# LoRa-Messenger-v1_1.net
KiCad netlist of a schematic drawn in EAGLE
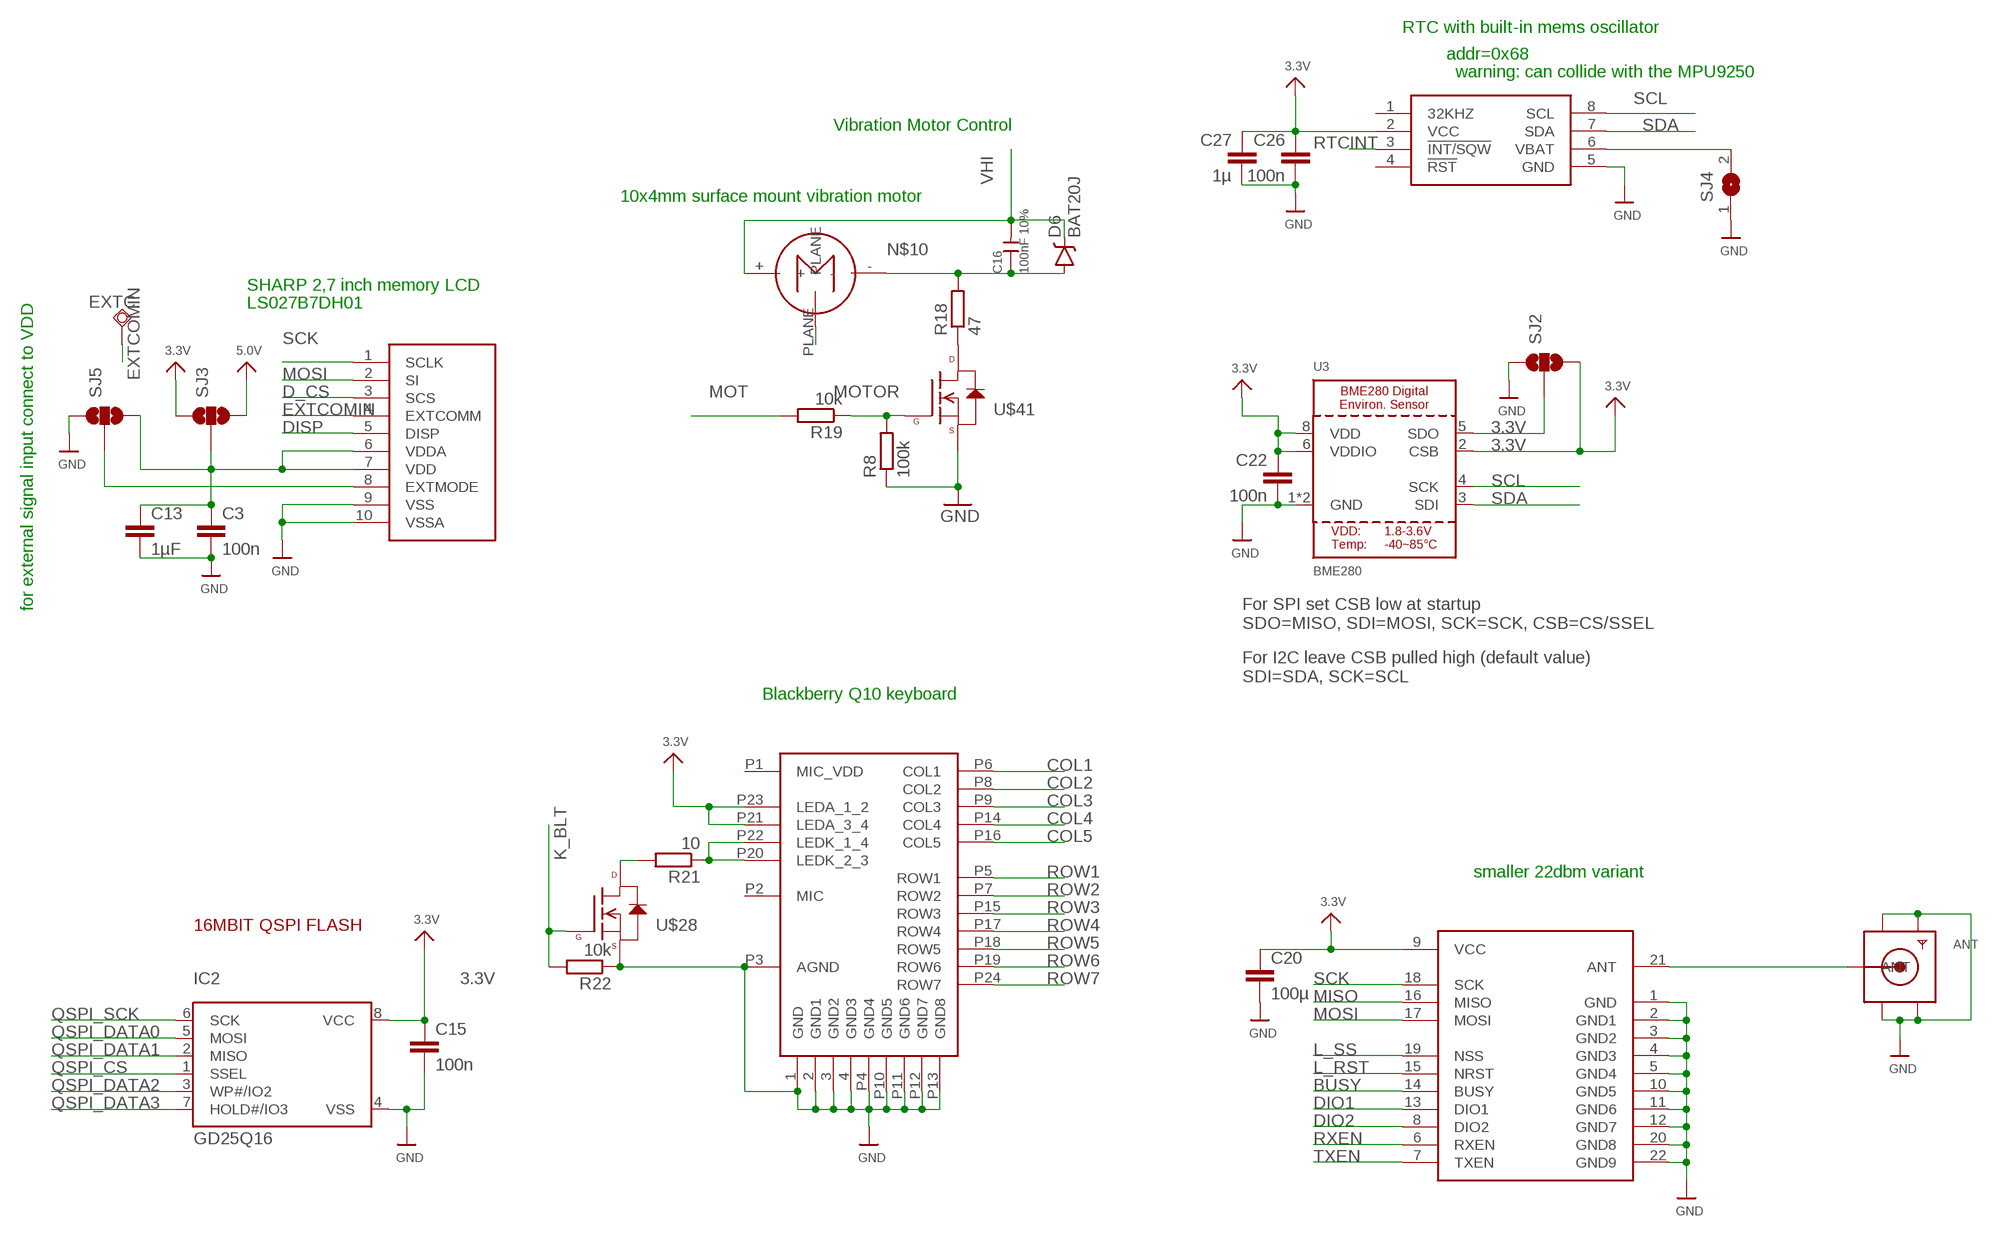
[diagram p0: schematic, sheet 1, part 1 of 3]
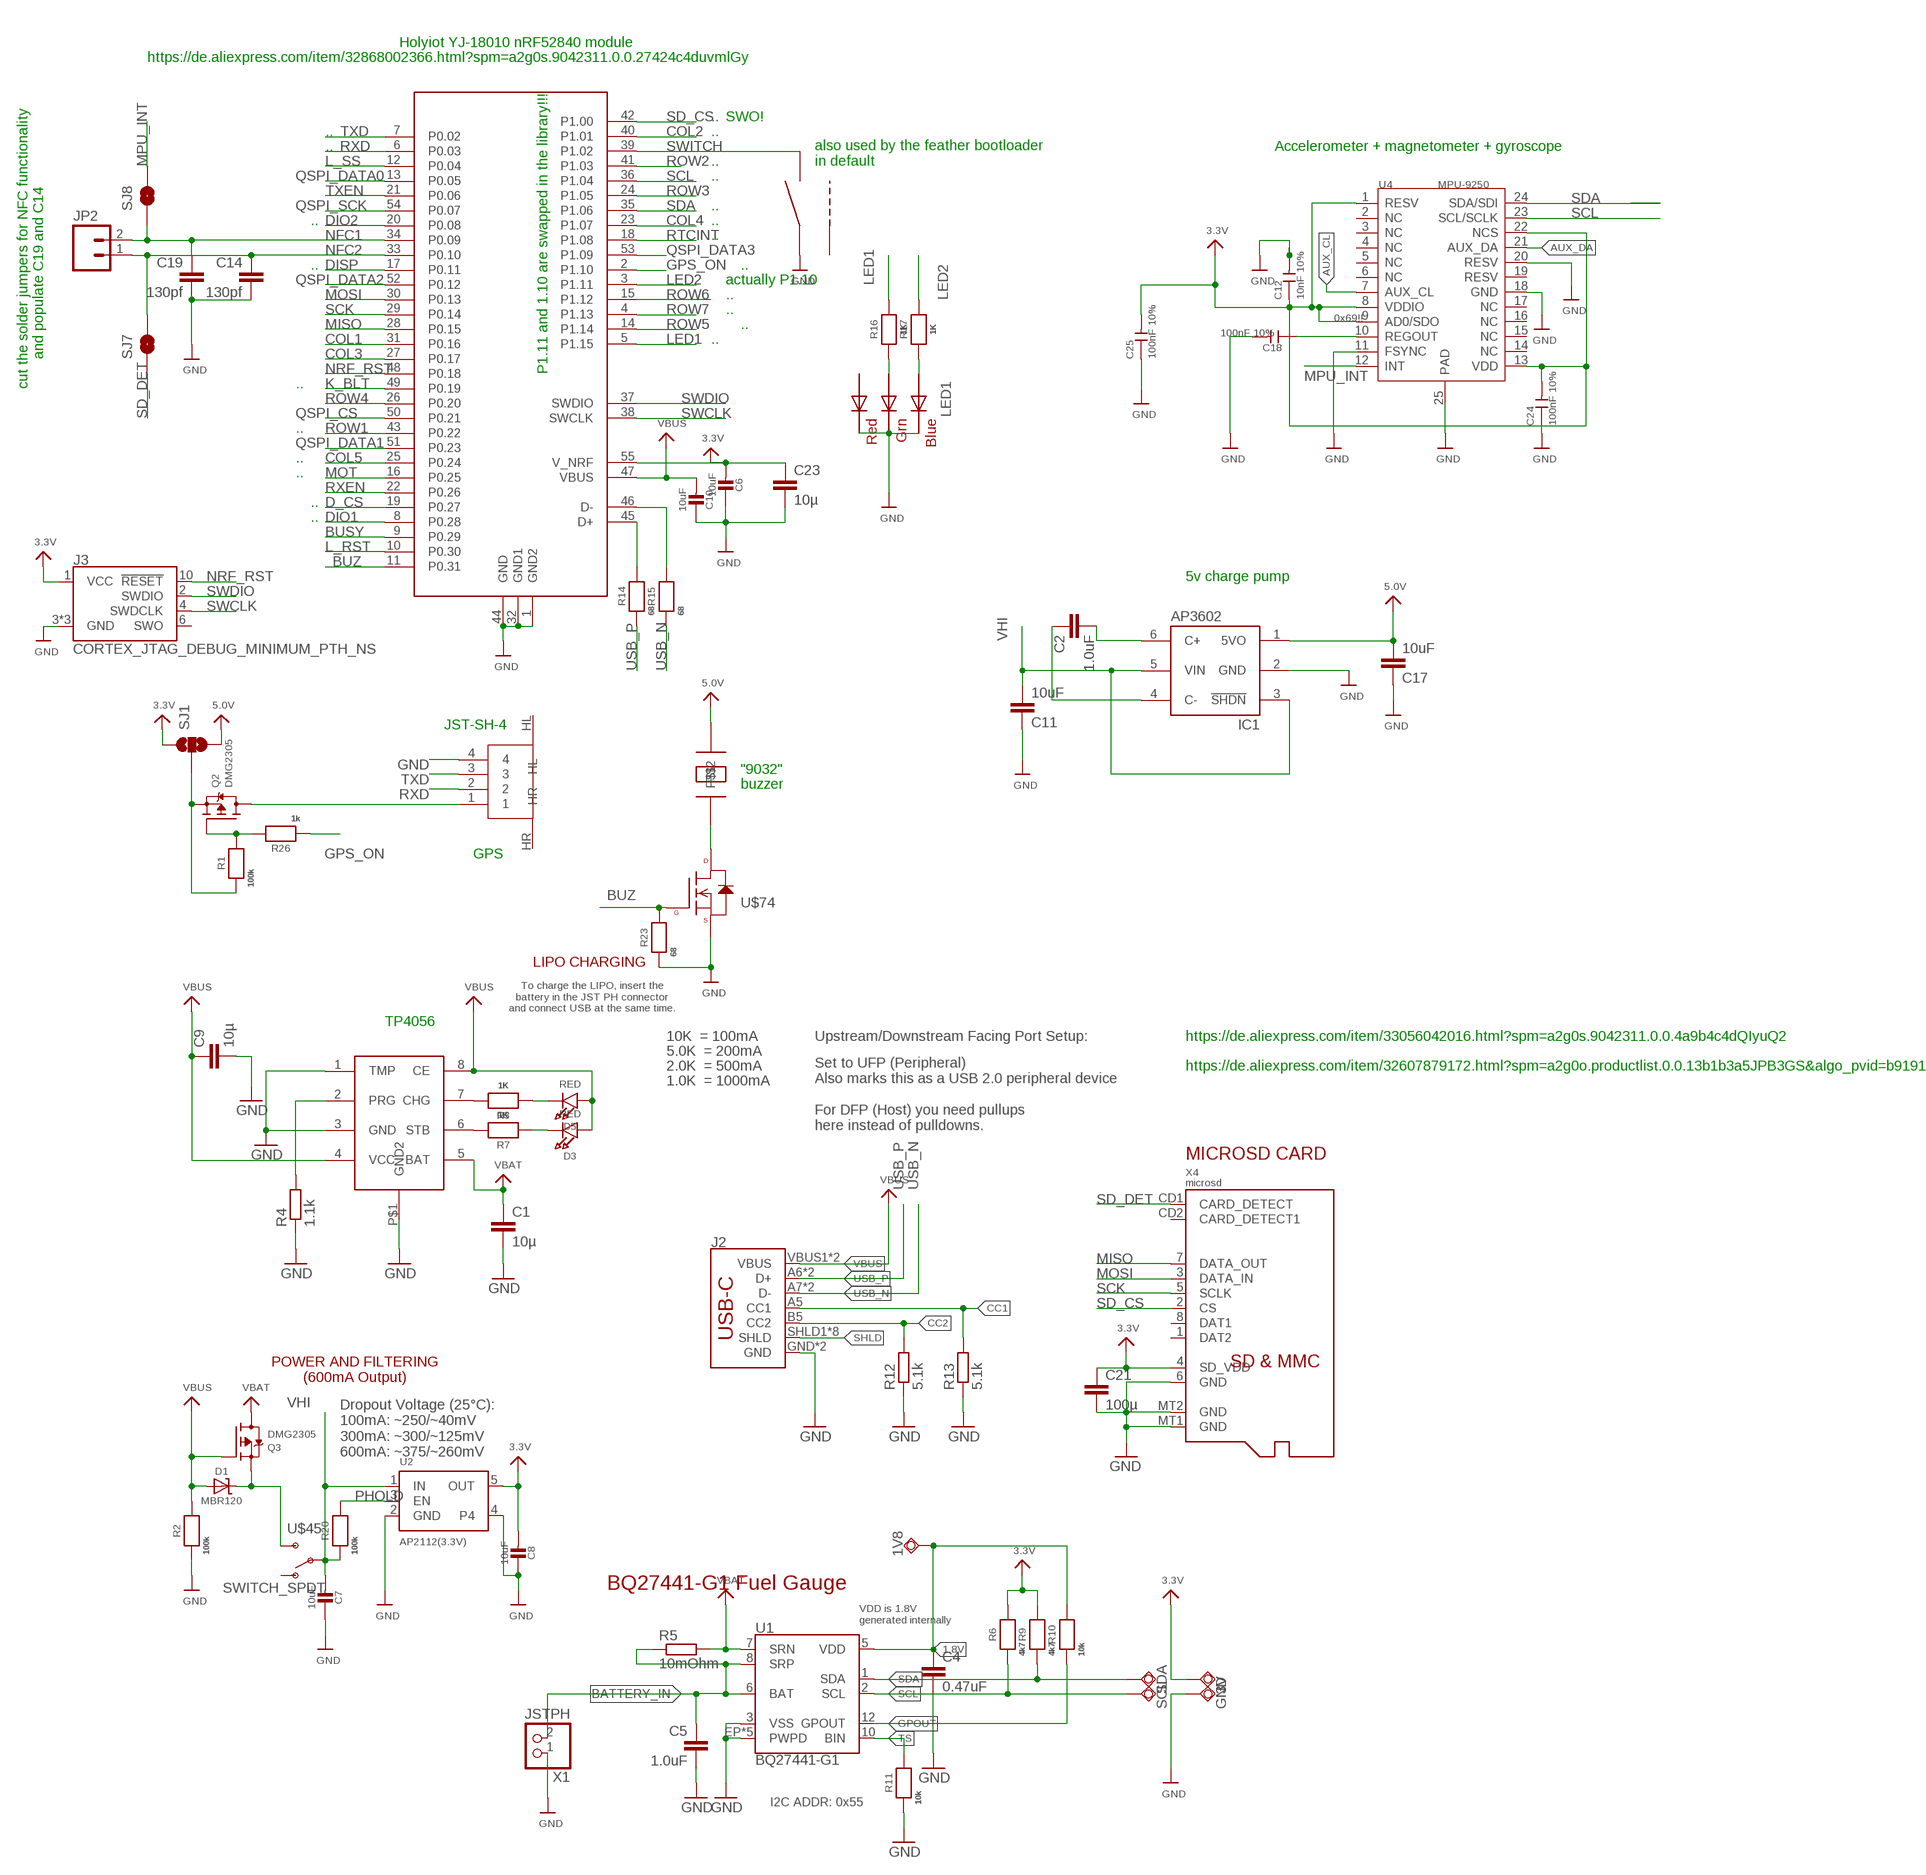
[diagram p1: schematic, sheet 1, part 2 of 3]
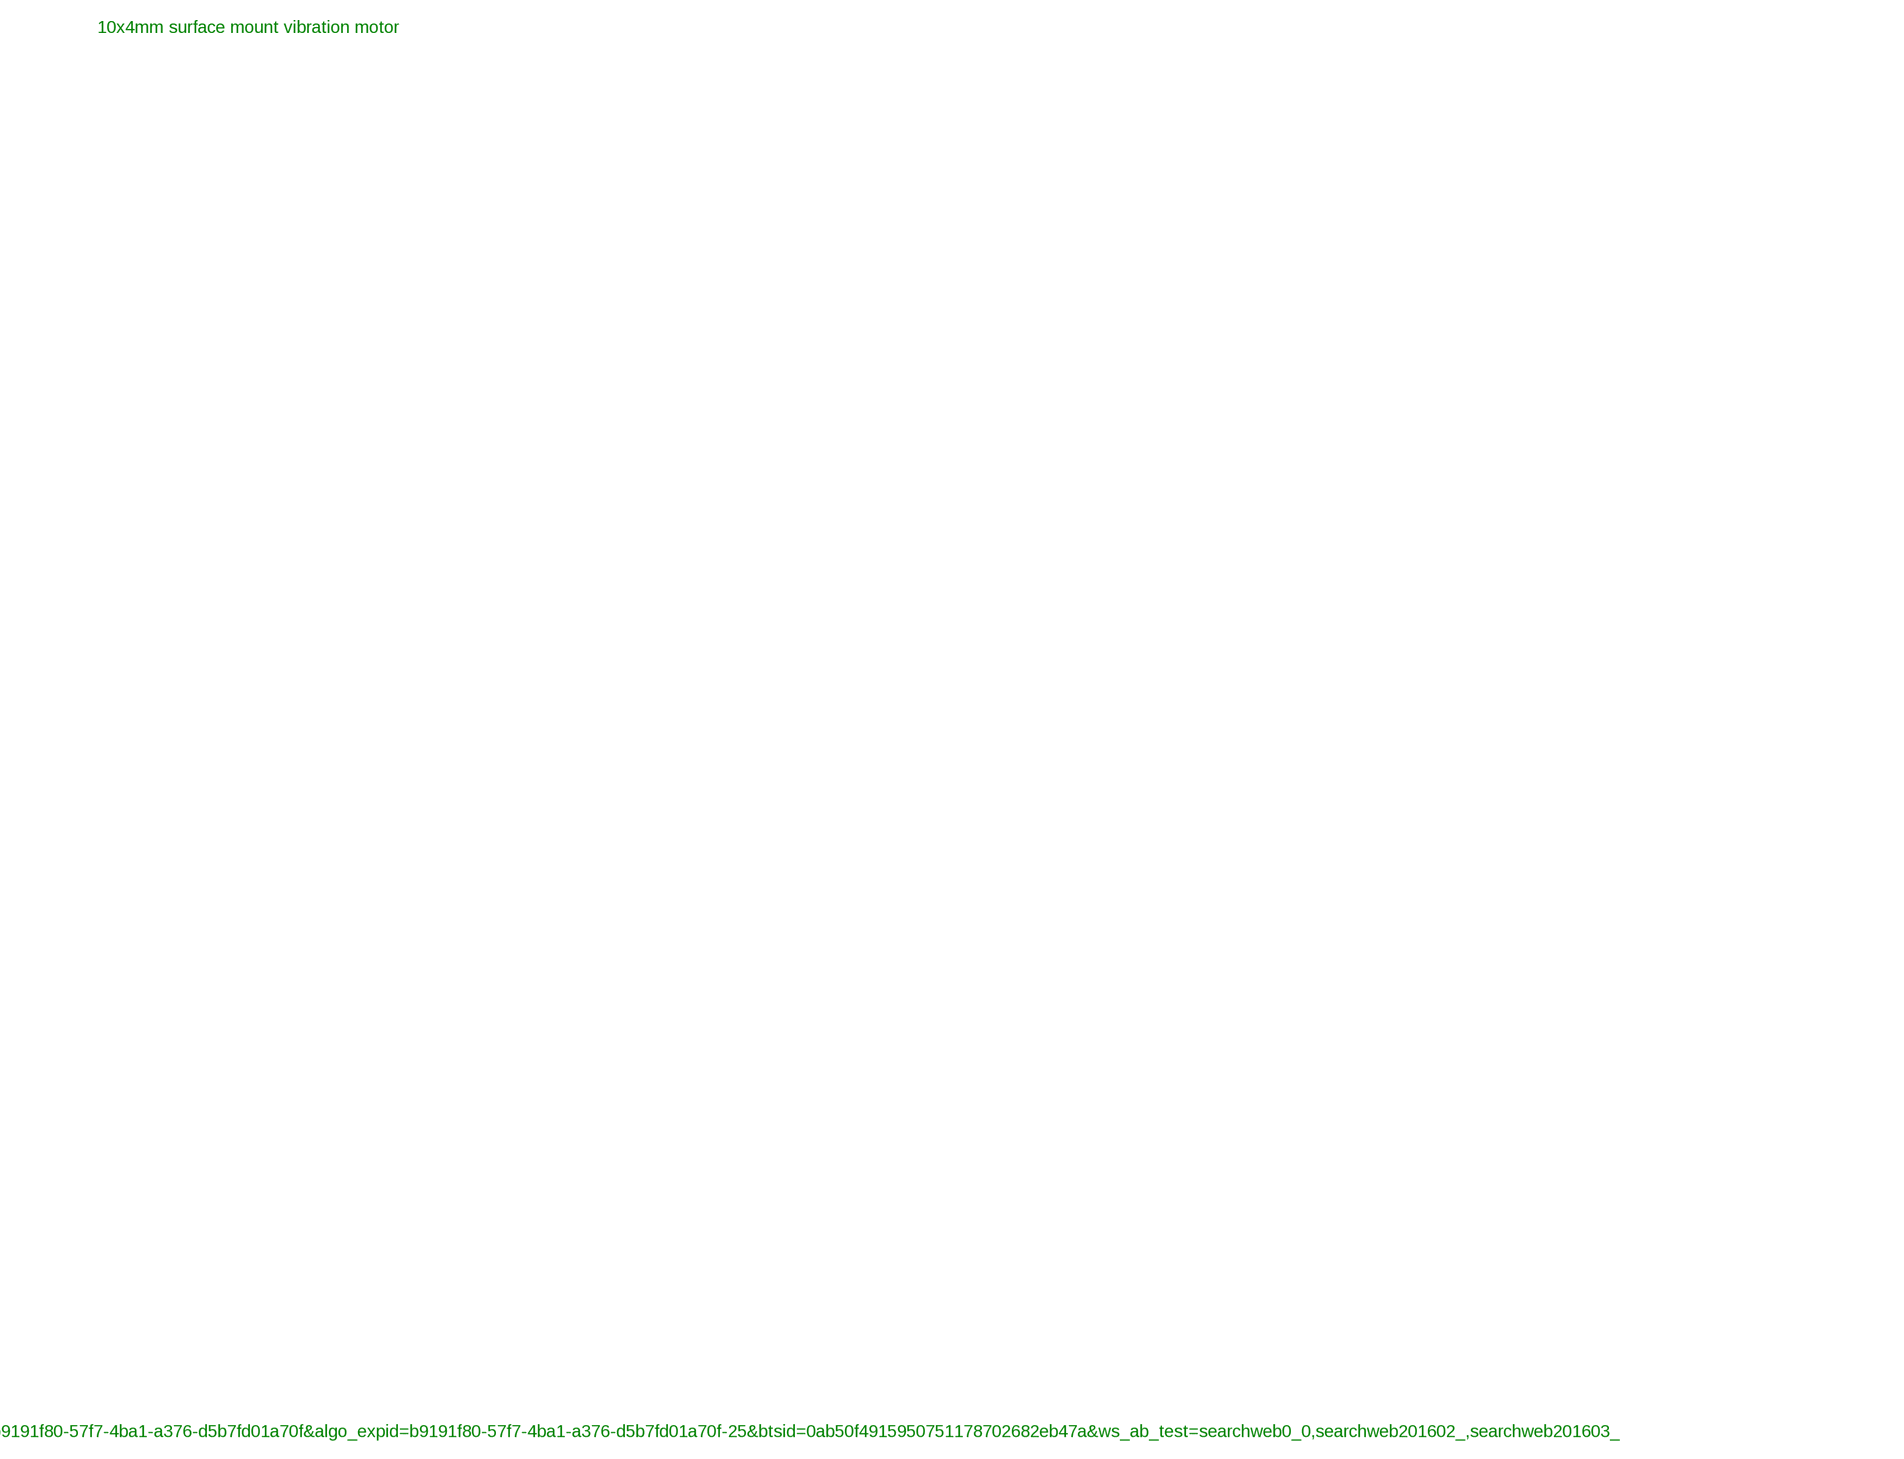
[diagram p2: schematic, sheet 1, part 3 of 3]

(export (version "E")
  (design (tool "Eeschema 10.0.6"))
  (components
    (comp (ref "1V8")
      (value "TPSQTP13R")
      (footprint "eagle-import:TP13R")
      (libsource (lib "eagle-import") (part "TPSQTP13R"))
    )
    (comp (ref "3V")
      (value "TPSQTP13R")
      (footprint "eagle-import:TP13R")
      (libsource (lib "eagle-import") (part "TPSQTP13R"))
    )
    (comp (ref "ANT")
      (value "SMACONNECTOR_EDGE")
      (footprint "eagle-import:SMA_EDGELAUNCH")
      (libsource (lib "eagle-import") (part "SMACONNECTOR_EDGE"))
    )
    (comp (ref "C1")
      (value "10µ")
      (footprint "eagle-import:C0805")
      (libsource (lib "eagle-import") (part "rcl_334_C-EUC0805"))
    )
    (comp (ref "C2")
      (value "1.0uF")
      (footprint "eagle-import:0603-CAP")
      (libsource (lib "eagle-import") (part "1.0UF-16V-10%(0603)"))
    )
    (comp (ref "C3")
      (value "100n")
      (footprint "eagle-import:C0402")
      (libsource (lib "eagle-import") (part "C-EUC0402"))
    )
    (comp (ref "C4")
      (value "0.47uF")
      (footprint "eagle-import:0603-CAP")
      (libsource (lib "eagle-import") (part "CAP0603-CAP"))
    )
    (comp (ref "C5")
      (value "1.0uF")
      (footprint "eagle-import:0603-CAP")
      (libsource (lib "eagle-import") (part "1.0UF-16V-10%(0603)"))
    )
    (comp (ref "C6")
      (value "10uF")
      (footprint "eagle-import:0805-NO")
      (libsource (lib "eagle-import") (part "CAP_CERAMIC0805-NOOUTLINE"))
    )
    (comp (ref "C7")
      (value "10uF")
      (footprint "eagle-import:0805-NO")
      (libsource (lib "eagle-import") (part "CAP_CERAMIC0805-NOOUTLINE"))
    )
    (comp (ref "C8")
      (value "10uF")
      (footprint "eagle-import:0805-NO")
      (libsource (lib "eagle-import") (part "CAP_CERAMIC0805-NOOUTLINE"))
    )
    (comp (ref "C9")
      (value "10µ")
      (footprint "eagle-import:C0805")
      (libsource (lib "eagle-import") (part "rcl_334_C-EUC0805"))
    )
    (comp (ref "C10")
      (value "10uF")
      (footprint "eagle-import:0805-NO")
      (libsource (lib "eagle-import") (part "CAP_CERAMIC0805-NOOUTLINE"))
    )
    (comp (ref "C11")
      (value "10uF")
      (footprint "eagle-import:0603-CAP")
      (libsource (lib "eagle-import") (part "1.0UF-16V-10%(0603)"))
    )
    (comp (ref "C12")
      (value "10nF 10%")
      (footprint "eagle-import:C0603")
      (libsource (lib "eagle-import") (part "CAP-0603"))
    )
    (comp (ref "C13")
      (value "1µF")
      (footprint "eagle-import:C0402")
      (libsource (lib "eagle-import") (part "C-EUC0402"))
    )
    (comp (ref "C14")
      (value "130pf")
      (footprint "eagle-import:0603-CAP")
      (libsource (lib "eagle-import") (part "1.0UF-16V-10%(0603)"))
    )
    (comp (ref "C15")
      (value "100n")
      (footprint "eagle-import:C0402")
      (libsource (lib "eagle-import") (part "C-EUC0402"))
    )
    (comp (ref "C16")
      (value "100nF 10%")
      (footprint "eagle-import:C0603")
      (libsource (lib "eagle-import") (part "CAP-0603"))
    )
    (comp (ref "C17")
      (value "10uF")
      (footprint "eagle-import:0603-CAP")
      (libsource (lib "eagle-import") (part "1.0UF-16V-10%(0603)"))
    )
    (comp (ref "C18")
      (value "100nF 10%")
      (footprint "eagle-import:C0603")
      (libsource (lib "eagle-import") (part "CAP-0603"))
    )
    (comp (ref "C19")
      (value "130pf")
      (footprint "eagle-import:0603-CAP")
      (libsource (lib "eagle-import") (part "1.0UF-16V-10%(0603)"))
    )
    (comp (ref "C20")
      (value "100µ")
      (footprint "eagle-import:C1206")
      (libsource (lib "eagle-import") (part "rcl_334_C-EUC1206"))
    )
    (comp (ref "C21")
      (value "100µ")
      (footprint "eagle-import:C1206")
      (libsource (lib "eagle-import") (part "rcl_334_C-EUC1206"))
    )
    (comp (ref "C22")
      (value "100n")
      (footprint "eagle-import:0603-CAP")
      (libsource (lib "eagle-import") (part "1.0UF-16V-10%(0603)"))
    )
    (comp (ref "C23")
      (value "10µ")
      (footprint "eagle-import:C0805")
      (libsource (lib "eagle-import") (part "rcl_334_C-EUC0805"))
    )
    (comp (ref "C24")
      (value "100nF 10%")
      (footprint "eagle-import:C0603")
      (libsource (lib "eagle-import") (part "CAP-0603"))
    )
    (comp (ref "C25")
      (value "100nF 10%")
      (footprint "eagle-import:C0603")
      (libsource (lib "eagle-import") (part "CAP-0603"))
    )
    (comp (ref "C26")
      (value "100n")
      (footprint "eagle-import:0603-CAP")
      (libsource (lib "eagle-import") (part "1.0UF-16V-10%(0603)"))
    )
    (comp (ref "C27")
      (value "1µ")
      (footprint "eagle-import:0603-CAP")
      (libsource (lib "eagle-import") (part "1.0UF-16V-10%(0603)"))
    )
    (comp (ref "D1")
      (value "MBR120")
      (footprint "eagle-import:SOD-123")
      (libsource (lib "eagle-import") (part "DIODE-SCHOTTKYSOD-123"))
    )
    (comp (ref "D3")
      (value "RED")
      (footprint "eagle-import:CHIPLED_0805_NOOUTLINE")
      (libsource (lib "eagle-import") (part "LED0805_NOOUTLINE"))
    )
    (comp (ref "D5")
      (value "RED")
      (footprint "eagle-import:CHIPLED_0805_NOOUTLINE")
      (libsource (lib "eagle-import") (part "LED0805_NOOUTLINE"))
    )
    (comp (ref "D6")
      (value "BAT20J")
      (footprint "eagle-import:SOD-323")
      (libsource (lib "eagle-import") (part "DIODE-SCHOTTKY-BAT20J"))
    )
    (comp (ref "DWN2")
      (value "LS12T2")
      (footprint "eagle-import:LS12T2")
      (libsource (lib "eagle-import") (part "LS12T2"))
    )
    (comp (ref "EXTC.")
      (value "TPSQTP13R")
      (footprint "eagle-import:TP13R")
      (libsource (lib "eagle-import") (part "TPSQTP13R"))
    )
    (comp (ref "GND")
      (value "TPSQTP13R")
      (footprint "eagle-import:TP13R")
      (libsource (lib "eagle-import") (part "TPSQTP13R"))
    )
    (comp (ref "IC1")
      (value "AP3602")
      (footprint "eagle-import:SOT23-6")
      (libsource (lib "eagle-import") (part "AP3602"))
    )
    (comp (ref "IC2")
      (value "GD25Q16")
      (footprint "eagle-import:USON8")
      (libsource (lib "eagle-import") (part "SPIFLASH_8PINUX"))
    )
    (comp (ref "J2")
      (value "USB_C16PIN")
      (footprint "eagle-import:USB-C-16P")
      (libsource (lib "eagle-import") (part "USB_C16PIN"))
    )
    (comp (ref "J3")
      (value "CORTEX_JTAG_DEBUG_MINIMUM_PTH_NS")
      (footprint "eagle-import:2X5-PTH-1.27MM-NO_SILK")
      (libsource (lib "eagle-import") (part "CORTEX_JTAG_DEBUG_MINIMUM_PTH_NS"))
    )
    (comp (ref "JP2")
      (value "M02PTH")
      (footprint "eagle-import:1X02")
      (libsource (lib "eagle-import") (part "M02PTH"))
    )
    (comp (ref "LED1")
      (value "RGBLED5050")
      (footprint "eagle-import:RGBLED5050")
      (libsource (lib "eagle-import") (part "RGBLED5050"))
    )
    (comp (ref "Q2")
      (value "DMG2305")
      (footprint "eagle-import:SOT23-R")
      (libsource (lib "eagle-import") (part "MOSFET-P"))
    )
    (comp (ref "Q3")
      (value "DMG2305")
      (footprint "eagle-import:SOT23-R")
      (libsource (lib "eagle-import") (part "MOSFET-P"))
    )
    (comp (ref "R1")
      (value "100k")
      (footprint "eagle-import:0603-NO")
      (libsource (lib "eagle-import") (part "RESISTOR_0603_NOOUT"))
    )
    (comp (ref "R2")
      (value "100k")
      (footprint "eagle-import:0603-NO")
      (libsource (lib "eagle-import") (part "RESISTOR_0603_NOOUT"))
    )
    (comp (ref "R3")
      (value "1K")
      (footprint "eagle-import:0603-NO")
      (libsource (lib "eagle-import") (part "RESISTOR_0603_NOOUT"))
    )
    (comp (ref "R4")
      (value "1.1k")
      (footprint "eagle-import:R0603")
      (libsource (lib "eagle-import") (part "rcl_334_R-EU_R0603"))
    )
    (comp (ref "R5")
      (value "10mOhm")
      (footprint "eagle-import:R0805")
      (libsource (lib "eagle-import") (part "rcl_334_R-EU_R0805"))
    )
    (comp (ref "R6")
      (value "4k7")
      (footprint "eagle-import:0603-NO")
      (libsource (lib "eagle-import") (part "RESISTOR_0603_NOOUT"))
    )
    (comp (ref "R7")
      (value "1K")
      (footprint "eagle-import:0603-NO")
      (libsource (lib "eagle-import") (part "RESISTOR_0603_NOOUT"))
    )
    (comp (ref "R8")
      (value "100k")
      (footprint "eagle-import:R0603")
      (libsource (lib "eagle-import") (part "R-EU_R0603"))
    )
    (comp (ref "R9")
      (value "4k7")
      (footprint "eagle-import:0603-NO")
      (libsource (lib "eagle-import") (part "RESISTOR_0603_NOOUT"))
    )
    (comp (ref "R10")
      (value "10k")
      (footprint "eagle-import:0603-NO")
      (libsource (lib "eagle-import") (part "RESISTOR_0603_NOOUT"))
    )
    (comp (ref "R11")
      (value "10k")
      (footprint "eagle-import:0603-NO")
      (libsource (lib "eagle-import") (part "RESISTOR_0603_NOOUT"))
    )
    (comp (ref "R12")
      (value "5.1k")
      (footprint "eagle-import:R0603")
      (libsource (lib "eagle-import") (part "rcl_334_R-EU_R0603"))
    )
    (comp (ref "R13")
      (value "5.1k")
      (footprint "eagle-import:R0603")
      (libsource (lib "eagle-import") (part "rcl_334_R-EU_R0603"))
    )
    (comp (ref "R14")
      (value "68")
      (footprint "eagle-import:0603-NO")
      (libsource (lib "eagle-import") (part "RESISTOR_0603_NOOUT"))
    )
    (comp (ref "R15")
      (value "68")
      (footprint "eagle-import:0603-NO")
      (libsource (lib "eagle-import") (part "RESISTOR_0603_NOOUT"))
    )
    (comp (ref "R16")
      (value "1K")
      (footprint "eagle-import:0603-NO")
      (libsource (lib "eagle-import") (part "RESISTOR_0603_NOOUT"))
    )
    (comp (ref "R17")
      (value "1K")
      (footprint "eagle-import:0603-NO")
      (libsource (lib "eagle-import") (part "RESISTOR_0603_NOOUT"))
    )
    (comp (ref "R18")
      (value "47")
      (footprint "eagle-import:R0603")
      (libsource (lib "eagle-import") (part "R-EU_R0603"))
    )
    (comp (ref "R19")
      (value "10k")
      (footprint "eagle-import:R0603")
      (libsource (lib "eagle-import") (part "R-EU_R0603"))
    )
    (comp (ref "R20")
      (value "100k")
      (footprint "eagle-import:0603-NO")
      (libsource (lib "eagle-import") (part "RESISTOR_0603_NOOUT"))
    )
    (comp (ref "R21")
      (value "10")
      (footprint "eagle-import:R0603")
      (libsource (lib "eagle-import") (part "R-EU_R0603"))
    )
    (comp (ref "R22")
      (value "10k")
      (footprint "eagle-import:R0603")
      (libsource (lib "eagle-import") (part "R-EU_R0603"))
    )
    (comp (ref "R23")
      (value "68")
      (footprint "eagle-import:0603-NO")
      (libsource (lib "eagle-import") (part "RESISTOR_0603_NOOUT"))
    )
    (comp (ref "R26")
      (value "1k")
      (footprint "eagle-import:0603-NO")
      (libsource (lib "eagle-import") (part "RESISTOR_0603_NOOUT"))
    )
    (comp (ref "SCL")
      (value "TPSQTP13R")
      (footprint "eagle-import:TP13R")
      (libsource (lib "eagle-import") (part "TPSQTP13R"))
    )
    (comp (ref "SDA")
      (value "TPSQTP13R")
      (footprint "eagle-import:TP13R")
      (libsource (lib "eagle-import") (part "TPSQTP13R"))
    )
    (comp (ref "SJ1")
      (value "SOLDERJUMPER_2WAY-OLDS")
      (footprint "eagle-import:SJ_3")
      (libsource (lib "eagle-import") (part "SOLDERJUMPER_2WAY-OLDS"))
    )
    (comp (ref "SJ2")
      (value "SOLDERJUMPER_2WAY-OLDS")
      (footprint "eagle-import:SJ_3")
      (libsource (lib "eagle-import") (part "SOLDERJUMPER_2WAY-OLDS"))
    )
    (comp (ref "SJ3")
      (value "SOLDERJUMPER_2WAY-OLDS")
      (footprint "eagle-import:SJ_3")
      (libsource (lib "eagle-import") (part "SOLDERJUMPER_2WAY-OLDS"))
    )
    (comp (ref "SJ4") (value "SJ") (footprint "eagle-import:SJ") (libsource (lib "eagle-import") (part "SJ")))
    (comp (ref "SJ5")
      (value "SOLDERJUMPER_2WAY-OLDS")
      (footprint "eagle-import:SJ_3")
      (libsource (lib "eagle-import") (part "SOLDERJUMPER_2WAY-OLDS"))
    )
    (comp (ref "SJ7")
      (value "SOLDERJUMPERTRACE")
      (footprint "eagle-import:SJ_2S-TRACE")
      (libsource (lib "eagle-import") (part "SOLDERJUMPERTRACE"))
    )
    (comp (ref "SJ8")
      (value "SOLDERJUMPERTRACE")
      (footprint "eagle-import:SJ_2S-TRACE")
      (libsource (lib "eagle-import") (part "SOLDERJUMPERTRACE"))
    )
    (comp (ref "U$2")
      (value "BUZZER")
      (footprint "eagle-import:BUZZER")
      (libsource (lib "eagle-import") (part "BUZZER"))
    )
    (comp (ref "U$7")
      (value "Q10KEYBOARD")
      (footprint "eagle-import:Q10KEYBOARD")
      (libsource (lib "eagle-import") (part "Q10KEYBOARD"))
    )
    (comp (ref "U$10")
      (value "AYF531035_SHARP_MEM_DISP")
      (footprint "eagle-import:AYF531035_Y5BW")
      (libsource (lib "eagle-import") (part "AYF531035_SHARP_MEM_DISP"))
    )
    (comp (ref "U$14")
      (value "NRF52840")
      (footprint "eagle-import:NRF52840MOD")
      (libsource (lib "eagle-import") (part "NRF52840"))
    )
    (comp (ref "U$17")
      (value "JST-SH-3")
      (footprint "eagle-import:JST-SH-3")
      (libsource (lib "eagle-import") (part "JST-SH-3"))
    )
    (comp (ref "U$28")
      (value "N-CHANNEL-MOSFET-BSS138")
      (footprint "eagle-import:SOT23-3")
      (libsource (lib "eagle-import") (part "N-CHANNEL-MOSFET-BSS138"))
    )
    (comp (ref "U$36")
      (value "SX1292-EBYTE")
      (footprint "eagle-import:SX1262_EBYTE")
      (libsource (lib "eagle-import") (part "SX1292-EBYTE"))
    )
    (comp (ref "U$41")
      (value "N-CHANNEL-MOSFET-BSS138")
      (footprint "eagle-import:SOT23-3")
      (libsource (lib "eagle-import") (part "N-CHANNEL-MOSFET-BSS138"))
    )
    (comp (ref "U$45")
      (value "SWITCH_SPDT")
      (footprint "eagle-import:KPS-1290")
      (libsource (lib "eagle-import") (part "SWITCH_SPDT"))
    )
    (comp (ref "U$46")
      (value "VIBRO")
      (footprint "eagle-import:VIBRO")
      (libsource (lib "eagle-import") (part "VIBRO"))
    )
    (comp (ref "U$47")
      (value "TP4056BETTER_TP4056")
      (footprint "eagle-import:TP4056BETTER_SO-08")
      (libsource (lib "eagle-import") (part "TP4056BETTER_TP4056"))
    )
    (comp (ref "U$69")
      (value "DS3231M")
      (footprint "eagle-import:SO8")
      (libsource (lib "eagle-import") (part "DS3231M"))
    )
    (comp (ref "U$74")
      (value "N-CHANNEL-MOSFET-BSS138")
      (footprint "eagle-import:SOT23-3")
      (libsource (lib "eagle-import") (part "N-CHANNEL-MOSFET-BSS138"))
    )
    (comp (ref "U1")
      (value "BQ27441-G1")
      (footprint "eagle-import:PDSO-N12")
      (libsource (lib "eagle-import") (part "BQ27441-G1"))
    )
    (comp (ref "U2")
      (value "AP2112(3.3V)")
      (footprint "eagle-import:SOT23-5")
      (libsource (lib "eagle-import") (part "VREG_SOT23-5"))
    )
    (comp (ref "U3")
      (value "BME280")
      (footprint "eagle-import:BME280")
      (libsource (lib "eagle-import") (part "BME280"))
    )
    (comp (ref "U4")
      (value "MPU-9250")
      (footprint "eagle-import:LEAD-QFN24")
      (libsource (lib "eagle-import") (part "MPU-9250"))
    )
    (comp (ref "X1")
      (value "JSTPH")
      (footprint "eagle-import:JSTPH2")
      (libsource (lib "eagle-import") (part "CON_JST_PH_2PIN"))
    )
    (comp (ref "X4")
      (value "microsd")
      (footprint "eagle-import:MICROSD")
      (libsource (lib "eagle-import") (part "MICROSD"))
    )
  )
  (nets
    (net (code "1") (name "/BUSY") (class "Default")
      (node (ref "U$14") (pin "9") (pinfunction "P0.29_9") (pintype "bidirectional"))
      (node (ref "U$36") (pin "14") (pinfunction "BUSY_14") (pintype "bidirectional"))
    )
    (net (code "2") (name "/BUZ") (class "Default")
      (node (ref "R23") (pin "2") (pinfunction "2_2") (pintype "passive"))
      (node (ref "U$14") (pin "11") (pinfunction "P0.31_11") (pintype "bidirectional"))
      (node (ref "U$74") (pin "1") (pinfunction "G_1") (pintype "passive"))
    )
    (net (code "3") (name "/COL1") (class "Default")
      (node (ref "U$14") (pin "31") (pinfunction "P0.16_31") (pintype "bidirectional"))
      (node (ref "U$7") (pin "P6") (pinfunction "COL1_P6") (pintype "bidirectional"))
    )
    (net (code "4") (name "/COL2") (class "Default")
      (node (ref "U$14") (pin "40") (pinfunction "P1.01_40") (pintype "bidirectional"))
      (node (ref "U$7") (pin "P8") (pinfunction "COL2_P8") (pintype "bidirectional"))
    )
    (net (code "5") (name "/COL3") (class "Default")
      (node (ref "U$14") (pin "27") (pinfunction "P0.17_27") (pintype "bidirectional"))
      (node (ref "U$7") (pin "P9") (pinfunction "COL3_P9") (pintype "bidirectional"))
    )
    (net (code "6") (name "/COL4") (class "Default")
      (node (ref "U$14") (pin "23") (pinfunction "P1.07_23") (pintype "bidirectional"))
      (node (ref "U$7") (pin "P14") (pinfunction "COL4_P14") (pintype "bidirectional"))
    )
    (net (code "7") (name "/COL5") (class "Default")
      (node (ref "U$14") (pin "25") (pinfunction "P0.24_25") (pintype "bidirectional"))
      (node (ref "U$7") (pin "P16") (pinfunction "COL5_P16") (pintype "bidirectional"))
    )
    (net (code "8") (name "/DIO1") (class "Default")
      (node (ref "U$14") (pin "8") (pinfunction "P0.28_8") (pintype "bidirectional"))
      (node (ref "U$36") (pin "13") (pinfunction "DIO1_13") (pintype "bidirectional"))
    )
    (net (code "9") (name "/DIO2") (class "Default")
      (node (ref "U$14") (pin "20") (pinfunction "P0.08_20") (pintype "bidirectional"))
      (node (ref "U$36") (pin "8") (pinfunction "DIO2_8") (pintype "bidirectional"))
    )
    (net (code "10") (name "/DISP") (class "Default")
      (node (ref "U$10") (pin "5") (pinfunction "DISP_5") (pintype "bidirectional"))
      (node (ref "U$14") (pin "17") (pinfunction "P0.11_17") (pintype "bidirectional"))
    )
    (net (code "11") (name "/D_CS") (class "Default")
      (node (ref "U$10") (pin "3") (pinfunction "SCS_3") (pintype "bidirectional"))
      (node (ref "U$14") (pin "19") (pinfunction "P0.27_19") (pintype "bidirectional"))
    )
    (net (code "12") (name "/EXTCOMIN") (class "Default")
      (node (ref "EXTC.") (pin "TP") (pinfunction "TP_TP") (pintype "input"))
      (node (ref "U$10") (pin "4") (pinfunction "EXTCOMM_4") (pintype "bidirectional"))
    )
    (net (code "13") (name "/GPS_ON") (class "Default")
      (node (ref "R26") (pin "1") (pinfunction "1_1") (pintype "passive"))
      (node (ref "U$14") (pin "2") (pinfunction "P1.10_2") (pintype "bidirectional"))
    )
    (net (code "14") (name "/K_BLT") (class "Default")
      (node (ref "R22") (pin "2") (pinfunction "2_2") (pintype "passive"))
      (node (ref "U$14") (pin "49") (pinfunction "P0.19_49") (pintype "bidirectional"))
      (node (ref "U$28") (pin "1") (pinfunction "G_1") (pintype "passive"))
    )
    (net (code "15") (name "/LED1") (class "Default")
      (node (ref "R16") (pin "2") (pinfunction "2_2") (pintype "passive"))
      (node (ref "U$14") (pin "5") (pinfunction "P1.15_5") (pintype "bidirectional"))
    )
    (net (code "16") (name "/LED2") (class "Default")
      (node (ref "R17") (pin "2") (pinfunction "2_2") (pintype "passive"))
      (node (ref "U$14") (pin "3") (pinfunction "P1.11_3") (pintype "bidirectional"))
    )
    (net (code "17") (name "/L_RST") (class "Default")
      (node (ref "U$14") (pin "10") (pinfunction "P0.30_10") (pintype "bidirectional"))
      (node (ref "U$36") (pin "15") (pinfunction "NRST_15") (pintype "bidirectional"))
    )
    (net (code "18") (name "/L_SS") (class "Default")
      (node (ref "U$14") (pin "12") (pinfunction "P0.04_12") (pintype "bidirectional"))
      (node (ref "U$36") (pin "19") (pinfunction "NSS_19") (pintype "bidirectional"))
    )
    (net (code "19") (name "/MISO") (class "Default")
      (node (ref "U$14") (pin "28") (pinfunction "P0.15_28") (pintype "bidirectional"))
      (node (ref "U$36") (pin "16") (pinfunction "MISO_16") (pintype "bidirectional"))
      (node (ref "X4") (pin "7") (pinfunction "DATA_OUT_7") (pintype "output"))
    )
    (net (code "20") (name "/MOSI") (class "Default")
      (node (ref "U$10") (pin "2") (pinfunction "SI_2") (pintype "bidirectional"))
      (node (ref "U$14") (pin "30") (pinfunction "P0.13_30") (pintype "bidirectional"))
      (node (ref "U$36") (pin "17") (pinfunction "MOSI_17") (pintype "bidirectional"))
      (node (ref "X4") (pin "3") (pinfunction "DATA_IN_3") (pintype "input"))
    )
    (net (code "21") (name "/MOT") (class "Default")
      (node (ref "R19") (pin "2") (pinfunction "2_2") (pintype "passive"))
      (node (ref "U$14") (pin "16") (pinfunction "P0.25_16") (pintype "bidirectional"))
    )
    (net (code "22") (name "/MOTOR") (class "Default")
      (node (ref "R19") (pin "1") (pinfunction "1_1") (pintype "passive"))
      (node (ref "R8") (pin "2") (pinfunction "2_2") (pintype "passive"))
      (node (ref "U$41") (pin "1") (pinfunction "G_1") (pintype "passive"))
    )
    (net (code "23") (name "/MPU_INT") (class "Default")
      (node (ref "SJ8") (pin "2") (pinfunction "2_2") (pintype "passive"))
      (node (ref "U4") (pin "12") (pinfunction "INT_12") (pintype "bidirectional"))
    )
    (net (code "24") (name "/N$10") (class "Default")
      (node (ref "C16") (pin "1") (pinfunction "1_1") (pintype "passive"))
      (node (ref "D6") (pin "A") (pinfunction "A_A") (pintype "passive"))
      (node (ref "R18") (pin "2") (pinfunction "2_2") (pintype "passive"))
      (node (ref "U$46") (pin "-") (pinfunction "-_-") (pintype "bidirectional"))
    )
    (net (code "25") (name "/NFC1") (class "Default")
      (node (ref "C19") (pin "1") (pinfunction "1_1") (pintype "passive"))
      (node (ref "JP2") (pin "2") (pinfunction "2_2") (pintype "passive"))
      (node (ref "SJ8") (pin "1") (pinfunction "1_1") (pintype "passive"))
      (node (ref "U$14") (pin "34") (pinfunction "P0.09_34") (pintype "bidirectional"))
    )
    (net (code "26") (name "/NFC2") (class "Default")
      (node (ref "C14") (pin "1") (pinfunction "1_1") (pintype "passive"))
      (node (ref "JP2") (pin "1") (pinfunction "1_1") (pintype "passive"))
      (node (ref "SJ7") (pin "2") (pinfunction "2_2") (pintype "passive"))
      (node (ref "U$14") (pin "33") (pinfunction "P0.10_33") (pintype "bidirectional"))
    )
    (net (code "27") (name "/NRF_RST") (class "Default")
      (node (ref "J3") (pin "10") (pinfunction "~{RESET}_10") (pintype "bidirectional"))
      (node (ref "U$14") (pin "48") (pinfunction "P0.18_48") (pintype "bidirectional"))
    )
    (net (code "28") (name "/PHOLD") (class "Default")
      (node (ref "R20") (pin "2") (pinfunction "2_2") (pintype "passive"))
      (node (ref "U2") (pin "3") (pinfunction "EN_3") (pintype "input"))
    )
    (net (code "29") (name "/QSPI_CS") (class "Default")
      (node (ref "IC2") (pin "1") (pinfunction "SSEL_1") (pintype "bidirectional"))
      (node (ref "U$14") (pin "50") (pinfunction "P0.21_50") (pintype "bidirectional"))
    )
    (net (code "30") (name "/QSPI_DATA0") (class "Default")
      (node (ref "IC2") (pin "5") (pinfunction "MOSI_5") (pintype "bidirectional"))
      (node (ref "U$14") (pin "13") (pinfunction "P0.05_13") (pintype "bidirectional"))
    )
    (net (code "31") (name "/QSPI_DATA1") (class "Default")
      (node (ref "IC2") (pin "2") (pinfunction "MISO_2") (pintype "bidirectional"))
      (node (ref "U$14") (pin "51") (pinfunction "P0.23_51") (pintype "bidirectional"))
    )
    (net (code "32") (name "/QSPI_DATA2") (class "Default")
      (node (ref "IC2") (pin "3") (pinfunction "WP#/IO2_3") (pintype "bidirectional"))
      (node (ref "U$14") (pin "52") (pinfunction "P0.12_52") (pintype "bidirectional"))
    )
    (net (code "33") (name "/QSPI_DATA3") (class "Default")
      (node (ref "IC2") (pin "7") (pinfunction "HOLD#/IO3_7") (pintype "bidirectional"))
      (node (ref "U$14") (pin "53") (pinfunction "P1.09_53") (pintype "bidirectional"))
    )
    (net (code "34") (name "/QSPI_SCK") (class "Default")
      (node (ref "IC2") (pin "6") (pinfunction "SCK_6") (pintype "bidirectional"))
      (node (ref "U$14") (pin "54") (pinfunction "P0.07_54") (pintype "bidirectional"))
    )
    (net (code "35") (name "/ROW1") (class "Default")
      (node (ref "U$14") (pin "43") (pinfunction "P0.22_43") (pintype "bidirectional"))
      (node (ref "U$7") (pin "P5") (pinfunction "ROW1_P5") (pintype "bidirectional"))
    )
    (net (code "36") (name "/ROW2") (class "Default")
      (node (ref "U$14") (pin "41") (pinfunction "P1.03_41") (pintype "bidirectional"))
      (node (ref "U$7") (pin "P7") (pinfunction "ROW2_P7") (pintype "bidirectional"))
    )
    (net (code "37") (name "/ROW3") (class "Default")
      (node (ref "U$14") (pin "24") (pinfunction "P1.05_24") (pintype "bidirectional"))
      (node (ref "U$7") (pin "P15") (pinfunction "ROW3_P15") (pintype "bidirectional"))
    )
    (net (code "38") (name "/ROW4") (class "Default")
      (node (ref "U$14") (pin "26") (pinfunction "P0.20_26") (pintype "bidirectional"))
      (node (ref "U$7") (pin "P17") (pinfunction "ROW4_P17") (pintype "bidirectional"))
    )
    (net (code "39") (name "/ROW5") (class "Default")
      (node (ref "U$14") (pin "14") (pinfunction "P1.14_14") (pintype "bidirectional"))
      (node (ref "U$7") (pin "P18") (pinfunction "ROW5_P18") (pintype "bidirectional"))
    )
    (net (code "40") (name "/ROW6") (class "Default")
      (node (ref "U$14") (pin "15") (pinfunction "P1.12_15") (pintype "bidirectional"))
      (node (ref "U$7") (pin "P19") (pinfunction "ROW6_P19") (pintype "bidirectional"))
    )
    (net (code "41") (name "/ROW7") (class "Default")
      (node (ref "U$14") (pin "4") (pinfunction "P1.13_4") (pintype "bidirectional"))
      (node (ref "U$7") (pin "P24") (pinfunction "ROW7_P24") (pintype "bidirectional"))
    )
    (net (code "42") (name "/RTCINT") (class "Default")
      (node (ref "U$14") (pin "18") (pinfunction "P1.08_18") (pintype "bidirectional"))
      (node (ref "U$69") (pin "3") (pinfunction "~{INT/SQW}_3") (pintype "bidirectional"))
    )
    (net (code "43") (name "/RXD") (class "Default")
      (node (ref "U$14") (pin "6") (pinfunction "P0.03_6") (pintype "bidirectional"))
      (node (ref "U$17") (pin "2") (pinfunction "2_2") (pintype "bidirectional"))
    )
    (net (code "44") (name "/RXEN") (class "Default")
      (node (ref "U$14") (pin "22") (pinfunction "P0.26_22") (pintype "bidirectional"))
      (node (ref "U$36") (pin "6") (pinfunction "RXEN_6") (pintype "bidirectional"))
    )
    (net (code "45") (name "/SCK") (class "Default")
      (node (ref "U$10") (pin "1") (pinfunction "SCLK_1") (pintype "bidirectional"))
      (node (ref "U$14") (pin "29") (pinfunction "P0.14_29") (pintype "bidirectional"))
      (node (ref "U$36") (pin "18") (pinfunction "SCK_18") (pintype "bidirectional"))
      (node (ref "X4") (pin "5") (pinfunction "SCLK_5") (pintype "input"))
    )
    (net (code "46") (name "/SD_CS") (class "Default")
      (node (ref "U$14") (pin "42") (pinfunction "P1.00_42") (pintype "bidirectional"))
      (node (ref "X4") (pin "2") (pinfunction "CS_2") (pintype "input"))
    )
    (net (code "47") (name "/SD_DET") (class "Default")
      (node (ref "SJ7") (pin "1") (pinfunction "1_1") (pintype "passive"))
      (node (ref "X4") (pin "CD1") (pinfunction "CARD_DETECT_CD1") (pintype "passive"))
    )
    (net (code "48") (name "/SWCLK") (class "Default")
      (node (ref "J3") (pin "4") (pinfunction "SWDCLK_4") (pintype "bidirectional"))
      (node (ref "U$14") (pin "38") (pinfunction "SWCLK_38") (pintype "bidirectional"))
    )
    (net (code "49") (name "/SWDIO") (class "Default")
      (node (ref "J3") (pin "2") (pinfunction "SWDIO_2") (pintype "bidirectional"))
      (node (ref "U$14") (pin "37") (pinfunction "SWDIO_37") (pintype "bidirectional"))
    )
    (net (code "50") (name "/SWITCH") (class "Default")
      (node (ref "DWN2") (pin "1") (pinfunction "1_1") (pintype "bidirectional"))
      (node (ref "U$14") (pin "39") (pinfunction "P1.02_39") (pintype "bidirectional"))
    )
    (net (code "51") (name "/TXD") (class "Default")
      (node (ref "U$14") (pin "7") (pinfunction "P0.02_7") (pintype "bidirectional"))
      (node (ref "U$17") (pin "3") (pinfunction "3_3") (pintype "bidirectional"))
    )
    (net (code "52") (name "/TXEN") (class "Default")
      (node (ref "U$14") (pin "21") (pinfunction "P0.06_21") (pintype "bidirectional"))
      (node (ref "U$36") (pin "7") (pinfunction "TXEN_7") (pintype "bidirectional"))
    )
    (net (code "53") (name "/VHI") (class "Default")
      (node (ref "C11") (pin "2") (pinfunction "2_2") (pintype "passive"))
      (node (ref "C16") (pin "2") (pinfunction "2_2") (pintype "passive"))
      (node (ref "C7") (pin "2") (pinfunction "2_2") (pintype "passive"))
      (node (ref "D6") (pin "C") (pinfunction "C_C") (pintype "passive"))
      (node (ref "IC1") (pin "3") (pinfunction "~{SHDN}_3") (pintype "input"))
      (node (ref "IC1") (pin "5") (pinfunction "VIN_5") (pintype "power_in"))
      (node (ref "R20") (pin "1") (pinfunction "1_1") (pintype "passive"))
      (node (ref "U$45") (pin "P") (pinfunction "P_P") (pintype "passive"))
      (node (ref "U$46") (pin "+") (pinfunction "+_+") (pintype "bidirectional"))
      (node (ref "U2") (pin "1") (pinfunction "IN_1") (pintype "power_in"))
    )
    (net (code "54") (name "1.8V") (class "Default")
      (node (ref "1V8") (pin "TP") (pinfunction "TP_TP") (pintype "input"))
      (node (ref "C4") (pin "1") (pinfunction "1_1") (pintype "passive"))
      (node (ref "R10") (pin "2") (pinfunction "2_2") (pintype "passive"))
      (node (ref "U1") (pin "5") (pinfunction "VDD_5") (pintype "bidirectional"))
    )
    (net (code "55") (name "3.3V") (class "Default")
      (node (ref "3V") (pin "TP") (pinfunction "TP_TP") (pintype "input"))
      (node (ref "C12") (pin "1") (pinfunction "1_1") (pintype "passive"))
      (node (ref "C15") (pin "1") (pinfunction "1_1") (pintype "passive"))
      (node (ref "C20") (pin "1") (pinfunction "1_1") (pintype "passive"))
      (node (ref "C21") (pin "1") (pinfunction "1_1") (pintype "passive"))
      (node (ref "C22") (pin "1") (pinfunction "1_1") (pintype "passive"))
      (node (ref "C23") (pin "1") (pinfunction "1_1") (pintype "passive"))
      (node (ref "C24") (pin "2") (pinfunction "2_2") (pintype "passive"))
      (node (ref "C25") (pin "2") (pinfunction "2_2") (pintype "passive"))
      (node (ref "C26") (pin "1") (pinfunction "1_1") (pintype "passive"))
      (node (ref "C27") (pin "1") (pinfunction "1_1") (pintype "passive"))
      (node (ref "C6") (pin "2") (pinfunction "2_2") (pintype "passive"))
      (node (ref "C8") (pin "2") (pinfunction "2_2") (pintype "passive"))
      (node (ref "IC2") (pin "8") (pinfunction "VCC_8") (pintype "bidirectional"))
      (node (ref "J3") (pin "1") (pinfunction "VCC_1") (pintype "bidirectional"))
      (node (ref "R6") (pin "2") (pinfunction "2_2") (pintype "passive"))
      (node (ref "R9") (pin "2") (pinfunction "2_2") (pintype "passive"))
      (node (ref "SJ1") (pin "1") (pinfunction "1_1") (pintype "passive"))
      (node (ref "SJ2") (pin "3") (pinfunction "3_3") (pintype "passive"))
      (node (ref "SJ3") (pin "1") (pinfunction "1_1") (pintype "passive"))
      (node (ref "U$14") (pin "55") (pinfunction "V_NRF_55") (pintype "bidirectional"))
      (node (ref "U$36") (pin "9") (pinfunction "VCC_9") (pintype "bidirectional"))
      (node (ref "U$69") (pin "2") (pinfunction "VCC_2") (pintype "bidirectional"))
      (node (ref "U$7") (pin "P21") (pinfunction "LEDA_3_4_P21") (pintype "bidirectional"))
      (node (ref "U$7") (pin "P23") (pinfunction "LEDA_1_2_P23") (pintype "bidirectional"))
      (node (ref "U2") (pin "5") (pinfunction "OUT_5") (pintype "power_in"))
      (node (ref "U3") (pin "2") (pinfunction "CSB_2") (pintype "input"))
      (node (ref "U3") (pin "6") (pinfunction "VDDIO_6") (pintype "power_in"))
      (node (ref "U3") (pin "8") (pinfunction "VDD_8") (pintype "power_in"))
      (node (ref "U4") (pin "1") (pinfunction "RESV_1") (pintype "bidirectional"))
      (node (ref "U4") (pin "13") (pinfunction "VDD_13") (pintype "bidirectional"))
      (node (ref "U4") (pin "22") (pinfunction "NCS_22") (pintype "bidirectional"))
      (node (ref "U4") (pin "8") (pinfunction "VDDIO_8") (pintype "bidirectional"))
      (node (ref "U4") (pin "9") (pinfunction "AD0/SDO_9") (pintype "bidirectional"))
      (node (ref "X4") (pin "4") (pinfunction "SD_VDD_4") (pintype "power_in"))
    )
    (net (code "56") (name "5.0V") (class "Default")
      (node (ref "C17") (pin "2") (pinfunction "2_2") (pintype "passive"))
      (node (ref "IC1") (pin "1") (pinfunction "5VO_1") (pintype "power_in"))
      (node (ref "SJ1") (pin "3") (pinfunction "3_3") (pintype "passive"))
      (node (ref "SJ3") (pin "3") (pinfunction "3_3") (pintype "passive"))
      (node (ref "U$2") (pin "P$1") (pinfunction "P$1_P$1") (pintype "bidirectional"))
    )
    (net (code "57") (name "AUX_CL") (class "Default")
      (node (ref "U4") (pin "7") (pinfunction "AUX_CL_7") (pintype "bidirectional"))
    )
    (net (code "58") (name "AUX_DA") (class "Default")
      (node (ref "U4") (pin "21") (pinfunction "AUX_DA_21") (pintype "bidirectional"))
    )
    (net (code "59") (name "BATTERY_IN") (class "Default")
      (node (ref "C5") (pin "1") (pinfunction "1_1") (pintype "passive"))
      (node (ref "R5") (pin "1") (pinfunction "1_1") (pintype "passive"))
      (node (ref "U1") (pin "6") (pinfunction "BAT_6") (pintype "bidirectional"))
      (node (ref "U1") (pin "8") (pinfunction "SRP_8") (pintype "bidirectional"))
      (node (ref "X1") (pin "2") (pinfunction "2_2") (pintype "passive"))
    )
    (net (code "60") (name "CC1") (class "Default")
      (node (ref "J2") (pin "A5") (pinfunction "CC1_A5") (pintype "bidirectional"))
      (node (ref "R13") (pin "2") (pinfunction "2_2") (pintype "passive"))
    )
    (net (code "61") (name "CC2") (class "Default")
      (node (ref "J2") (pin "B5") (pinfunction "CC2_B5") (pintype "bidirectional"))
      (node (ref "R12") (pin "2") (pinfunction "2_2") (pintype "passive"))
    )
    (net (code "62") (name "GND") (class "Default")
      (node (ref "ANT") (pin "GND@1") (pinfunction "GND4_GND@1") (pintype "power_in"))
      (node (ref "ANT") (pin "GND@2") (pinfunction "GND3_GND@2") (pintype "power_in"))
      (node (ref "ANT") (pin "GND@3") (pinfunction "GND2_GND@3") (pintype "power_in"))
      (node (ref "ANT") (pin "GND@4") (pinfunction "GND1_GND@4") (pintype "power_in"))
      (node (ref "C1") (pin "2") (pinfunction "2_2") (pintype "passive"))
      (node (ref "C10") (pin "1") (pinfunction "1_1") (pintype "passive"))
      (node (ref "C11") (pin "1") (pinfunction "1_1") (pintype "passive"))
      (node (ref "C12") (pin "2") (pinfunction "2_2") (pintype "passive"))
      (node (ref "C13") (pin "2") (pinfunction "2_2") (pintype "passive"))
      (node (ref "C14") (pin "2") (pinfunction "2_2") (pintype "passive"))
      (node (ref "C15") (pin "2") (pinfunction "2_2") (pintype "passive"))
      (node (ref "C17") (pin "1") (pinfunction "1_1") (pintype "passive"))
      (node (ref "C18") (pin "2") (pinfunction "2_2") (pintype "passive"))
      (node (ref "C19") (pin "2") (pinfunction "2_2") (pintype "passive"))
      (node (ref "C20") (pin "2") (pinfunction "2_2") (pintype "passive"))
      (node (ref "C21") (pin "2") (pinfunction "2_2") (pintype "passive"))
      (node (ref "C22") (pin "2") (pinfunction "2_2") (pintype "passive"))
      (node (ref "C23") (pin "2") (pinfunction "2_2") (pintype "passive"))
      (node (ref "C24") (pin "1") (pinfunction "1_1") (pintype "passive"))
      (node (ref "C25") (pin "1") (pinfunction "1_1") (pintype "passive"))
      (node (ref "C26") (pin "2") (pinfunction "2_2") (pintype "passive"))
      (node (ref "C27") (pin "2") (pinfunction "2_2") (pintype "passive"))
      (node (ref "C3") (pin "2") (pinfunction "2_2") (pintype "passive"))
      (node (ref "C4") (pin "2") (pinfunction "2_2") (pintype "passive"))
      (node (ref "C5") (pin "2") (pinfunction "2_2") (pintype "passive"))
      (node (ref "C6") (pin "1") (pinfunction "1_1") (pintype "passive"))
      (node (ref "C7") (pin "1") (pinfunction "1_1") (pintype "passive"))
      (node (ref "C8") (pin "1") (pinfunction "1_1") (pintype "passive"))
      (node (ref "C9") (pin "2") (pinfunction "2_2") (pintype "passive"))
      (node (ref "DWN2") (pin "2") (pinfunction "2_2") (pintype "bidirectional"))
      (node (ref "GND") (pin "TP") (pinfunction "TP_TP") (pintype "input"))
      (node (ref "IC1") (pin "2") (pinfunction "GND_2") (pintype "power_in"))
      (node (ref "IC2") (pin "4") (pinfunction "VSS_4") (pintype "bidirectional"))
      (node (ref "J2") (pin "GND") (pinfunction "GND_GND") (pintype "bidirectional"))
      (node (ref "J2") (pin "GND2") (pinfunction "GND_GND2") (pintype "bidirectional"))
      (node (ref "J3") (pin "3") (pinfunction "GND_3") (pintype "bidirectional"))
      (node (ref "J3") (pin "5") (pinfunction "GND_5") (pintype "bidirectional"))
      (node (ref "J3") (pin "9") (pinfunction "GND_9") (pintype "bidirectional"))
      (node (ref "LED1") (pin "4") (pinfunction "BLUE_C_4") (pintype "bidirectional"))
      (node (ref "LED1") (pin "5") (pinfunction "RED_C_5") (pintype "bidirectional"))
      (node (ref "LED1") (pin "6") (pinfunction "GREEN_C_6") (pintype "bidirectional"))
      (node (ref "R11") (pin "1") (pinfunction "1_1") (pintype "passive"))
      (node (ref "R12") (pin "1") (pinfunction "1_1") (pintype "passive"))
      (node (ref "R13") (pin "1") (pinfunction "1_1") (pintype "passive"))
      (node (ref "R2") (pin "1") (pinfunction "1_1") (pintype "passive"))
      (node (ref "R22") (pin "1") (pinfunction "1_1") (pintype "passive"))
      (node (ref "R23") (pin "1") (pinfunction "1_1") (pintype "passive"))
      (node (ref "R4") (pin "1") (pinfunction "1_1") (pintype "passive"))
      (node (ref "R8") (pin "1") (pinfunction "1_1") (pintype "passive"))
      (node (ref "SJ2") (pin "1") (pinfunction "1_1") (pintype "passive"))
      (node (ref "SJ4") (pin "1") (pinfunction "1_1") (pintype "passive"))
      (node (ref "SJ5") (pin "1") (pinfunction "1_1") (pintype "passive"))
      (node (ref "U$10") (pin "10") (pinfunction "VSSA_10") (pintype "bidirectional"))
      (node (ref "U$10") (pin "9") (pinfunction "VSS_9") (pintype "bidirectional"))
      (node (ref "U$14") (pin "1") (pinfunction "GND2_1") (pintype "bidirectional"))
      (node (ref "U$14") (pin "32") (pinfunction "GND1_32") (pintype "bidirectional"))
      (node (ref "U$14") (pin "44") (pinfunction "GND_44") (pintype "bidirectional"))
      (node (ref "U$17") (pin "4") (pinfunction "4_4") (pintype "bidirectional"))
      (node (ref "U$28") (pin "2") (pinfunction "S_2") (pintype "passive"))
      (node (ref "U$36") (pin "1") (pinfunction "GND_1") (pintype "bidirectional"))
      (node (ref "U$36") (pin "10") (pinfunction "GND5_10") (pintype "bidirectional"))
      (node (ref "U$36") (pin "11") (pinfunction "GND6_11") (pintype "bidirectional"))
      (node (ref "U$36") (pin "12") (pinfunction "GND7_12") (pintype "bidirectional"))
      (node (ref "U$36") (pin "2") (pinfunction "GND1_2") (pintype "bidirectional"))
      (node (ref "U$36") (pin "20") (pinfunction "GND8_20") (pintype "bidirectional"))
      (node (ref "U$36") (pin "22") (pinfunction "GND9_22") (pintype "bidirectional"))
      (node (ref "U$36") (pin "3") (pinfunction "GND2_3") (pintype "bidirectional"))
      (node (ref "U$36") (pin "4") (pinfunction "GND3_4") (pintype "bidirectional"))
      (node (ref "U$36") (pin "5") (pinfunction "GND4_5") (pintype "bidirectional"))
      (node (ref "U$41") (pin "2") (pinfunction "S_2") (pintype "passive"))
      (node (ref "U$47") (pin "1") (pinfunction "TMP_1") (pintype "bidirectional"))
      (node (ref "U$47") (pin "3") (pinfunction "GND_3") (pintype "bidirectional"))
      (node (ref "U$47") (pin "P$1") (pinfunction "GND2_P$1") (pintype "bidirectional"))
      (node (ref "U$69") (pin "5") (pinfunction "GND_5") (pintype "bidirectional"))
      (node (ref "U$7") (pin "1") (pinfunction "GND_1") (pintype "bidirectional"))
      (node (ref "U$7") (pin "2") (pinfunction "GND1_2") (pintype "bidirectional"))
      (node (ref "U$7") (pin "3") (pinfunction "GND2_3") (pintype "bidirectional"))
      (node (ref "U$7") (pin "4") (pinfunction "GND3_4") (pintype "bidirectional"))
      (node (ref "U$7") (pin "P10") (pinfunction "GND5_P10") (pintype "bidirectional"))
      (node (ref "U$7") (pin "P11") (pinfunction "GND6_P11") (pintype "bidirectional"))
      (node (ref "U$7") (pin "P12") (pinfunction "GND7_P12") (pintype "bidirectional"))
      (node (ref "U$7") (pin "P13") (pinfunction "GND8_P13") (pintype "bidirectional"))
      (node (ref "U$7") (pin "P3") (pinfunction "AGND_P3") (pintype "bidirectional"))
      (node (ref "U$7") (pin "P4") (pinfunction "GND4_P4") (pintype "bidirectional"))
      (node (ref "U$74") (pin "2") (pinfunction "S_2") (pintype "passive"))
      (node (ref "U1") (pin "3") (pinfunction "VSS_3") (pintype "bidirectional"))
      (node (ref "U1") (pin "EP") (pinfunction "PWPD_EP") (pintype "bidirectional"))
      (node (ref "U1") (pin "EP1") (pinfunction "PWPD_EP1") (pintype "bidirectional"))
      (node (ref "U1") (pin "EP2") (pinfunction "PWPD_EP2") (pintype "bidirectional"))
      (node (ref "U1") (pin "EP3") (pinfunction "PWPD_EP3") (pintype "bidirectional"))
      (node (ref "U1") (pin "EP4") (pinfunction "PWPD_EP4") (pintype "bidirectional"))
      (node (ref "U2") (pin "2") (pinfunction "GND_2") (pintype "power_in"))
      (node (ref "U2") (pin "4") (pinfunction "P4_4") (pintype "bidirectional"))
      (node (ref "U3") (pin "1") (pinfunction "GND_1") (pintype "power_in"))
      (node (ref "U3") (pin "7") (pinfunction "GND_7") (pintype "power_in"))
      (node (ref "U4") (pin "11") (pinfunction "FSYNC_11") (pintype "bidirectional"))
      (node (ref "U4") (pin "18") (pinfunction "GND_18") (pintype "bidirectional"))
      (node (ref "U4") (pin "20") (pinfunction "RESV_20") (pintype "bidirectional"))
      (node (ref "U4") (pin "25") (pinfunction "PAD_25") (pintype "bidirectional"))
      (node (ref "X1") (pin "1") (pinfunction "1_1") (pintype "passive"))
      (node (ref "X4") (pin "6") (pinfunction "GND_6") (pintype "power_in"))
      (node (ref "X4") (pin "MT1") (pinfunction "GND_MT1") (pintype "power_in"))
      (node (ref "X4") (pin "MT2") (pinfunction "GND_MT2") (pintype "power_in"))
    )
    (net (code "63") (name "GPOUT") (class "Default")
      (node (ref "R10") (pin "1") (pinfunction "1_1") (pintype "passive"))
      (node (ref "U1") (pin "12") (pinfunction "GPOUT_12") (pintype "bidirectional"))
    )
    (net (code "64") (name "Net-(ANT-ANT)") (class "Default")
      (node (ref "ANT") (pin "P") (pinfunction "ANT_P") (pintype "bidirectional"))
      (node (ref "U$36") (pin "21") (pinfunction "ANT_21") (pintype "bidirectional"))
    )
    (net (code "65") (name "Net-(D3-PadC)") (class "Default")
      (node (ref "D3") (pin "C") (pinfunction "C_C") (pintype "passive"))
      (node (ref "R7") (pin "1") (pinfunction "1_1") (pintype "passive"))
    )
    (net (code "66") (name "Net-(D5-PadC)") (class "Default")
      (node (ref "D5") (pin "C") (pinfunction "C_C") (pintype "passive"))
      (node (ref "R3") (pin "1") (pinfunction "1_1") (pintype "passive"))
    )
    (net (code "67") (name "Net-(IC1-C+)") (class "Default")
      (node (ref "C2") (pin "2") (pinfunction "2_2") (pintype "passive"))
      (node (ref "IC1") (pin "6") (pinfunction "C+_6") (pintype "bidirectional"))
    )
    (net (code "68") (name "Net-(IC1-C-)") (class "Default")
      (node (ref "C2") (pin "1") (pinfunction "1_1") (pintype "passive"))
      (node (ref "IC1") (pin "4") (pinfunction "C-_4") (pintype "bidirectional"))
    )
    (net (code "69") (name "Net-(LED1-BLUE_A)") (class "Default")
      (node (ref "LED1") (pin "3") (pinfunction "BLUE_A_3") (pintype "bidirectional"))
      (node (ref "R17") (pin "1") (pinfunction "1_1") (pintype "passive"))
    )
    (net (code "70") (name "Net-(LED1-GREEN_A)") (class "Default")
      (node (ref "LED1") (pin "1") (pinfunction "GREEN_A_1") (pintype "bidirectional"))
      (node (ref "R16") (pin "1") (pinfunction "1_1") (pintype "passive"))
    )
    (net (code "71") (name "Net-(Q2-D)") (class "Default")
      (node (ref "Q2") (pin "3") (pinfunction "D_3") (pintype "passive"))
      (node (ref "U$17") (pin "1") (pinfunction "1_1") (pintype "bidirectional"))
    )
    (net (code "72") (name "Net-(Q2-G)") (class "Default")
      (node (ref "Q2") (pin "1") (pinfunction "G_1") (pintype "passive"))
      (node (ref "R1") (pin "2") (pinfunction "2_2") (pintype "passive"))
      (node (ref "R26") (pin "2") (pinfunction "2_2") (pintype "passive"))
    )
    (net (code "73") (name "Net-(Q2-S)") (class "Default")
      (node (ref "Q2") (pin "2") (pinfunction "S_2") (pintype "passive"))
      (node (ref "R1") (pin "1") (pinfunction "1_1") (pintype "passive"))
      (node (ref "SJ1") (pin "2") (pinfunction "2_2") (pintype "passive"))
    )
    (net (code "74") (name "Net-(Q3-S)") (class "Default")
      (node (ref "D1") (pin "C") (pinfunction "C_C") (pintype "passive"))
      (node (ref "Q3") (pin "2") (pinfunction "S_2") (pintype "passive"))
      (node (ref "U$45") (pin "S") (pinfunction "S_S") (pintype "passive"))
    )
    (net (code "75") (name "Net-(U$7-LEDK_1_4)") (class "Default")
      (node (ref "R21") (pin "1") (pinfunction "1_1") (pintype "passive"))
      (node (ref "U$7") (pin "P20") (pinfunction "LEDK_2_3_P20") (pintype "bidirectional"))
      (node (ref "U$7") (pin "P22") (pinfunction "LEDK_1_4_P22") (pintype "bidirectional"))
    )
    (net (code "76") (name "Net-(U$10-EXTMODE)") (class "Default")
      (node (ref "SJ5") (pin "2") (pinfunction "2_2") (pintype "passive"))
      (node (ref "U$10") (pin "8") (pinfunction "EXTMODE_8") (pintype "bidirectional"))
    )
    (net (code "77") (name "Net-(U$10-VDD)") (class "Default")
      (node (ref "C13") (pin "1") (pinfunction "1_1") (pintype "passive"))
      (node (ref "C3") (pin "1") (pinfunction "1_1") (pintype "passive"))
      (node (ref "SJ3") (pin "2") (pinfunction "2_2") (pintype "passive"))
      (node (ref "SJ5") (pin "3") (pinfunction "3_3") (pintype "passive"))
      (node (ref "U$10") (pin "6") (pinfunction "VDDA_6") (pintype "bidirectional"))
      (node (ref "U$10") (pin "7") (pinfunction "VDD_7") (pintype "bidirectional"))
    )
    (net (code "78") (name "Net-(U$14-D+)") (class "Default")
      (node (ref "R14") (pin "2") (pinfunction "2_2") (pintype "passive"))
      (node (ref "U$14") (pin "45") (pinfunction "D+_45") (pintype "bidirectional"))
    )
    (net (code "79") (name "Net-(U$14-D-)") (class "Default")
      (node (ref "R15") (pin "2") (pinfunction "2_2") (pintype "passive"))
      (node (ref "U$14") (pin "46") (pinfunction "D-_46") (pintype "bidirectional"))
    )
    (net (code "80") (name "Net-(U$28-D)") (class "Default")
      (node (ref "R21") (pin "2") (pinfunction "2_2") (pintype "passive"))
      (node (ref "U$28") (pin "3") (pinfunction "D_3") (pintype "passive"))
    )
    (net (code "81") (name "Net-(U$41-D)") (class "Default")
      (node (ref "R18") (pin "1") (pinfunction "1_1") (pintype "passive"))
      (node (ref "U$41") (pin "3") (pinfunction "D_3") (pintype "passive"))
    )
    (net (code "82") (name "Net-(U$47-CHG)") (class "Default")
      (node (ref "R3") (pin "2") (pinfunction "2_2") (pintype "passive"))
      (node (ref "U$47") (pin "7") (pinfunction "CHG_7") (pintype "bidirectional"))
    )
    (net (code "83") (name "Net-(U$47-PRG)") (class "Default")
      (node (ref "R4") (pin "2") (pinfunction "2_2") (pintype "passive"))
      (node (ref "U$47") (pin "2") (pinfunction "PRG_2") (pintype "bidirectional"))
    )
    (net (code "84") (name "Net-(U$47-STB)") (class "Default")
      (node (ref "R7") (pin "2") (pinfunction "2_2") (pintype "passive"))
      (node (ref "U$47") (pin "6") (pinfunction "STB_6") (pintype "bidirectional"))
    )
    (net (code "85") (name "Net-(U$69-VBAT)") (class "Default")
      (node (ref "SJ4") (pin "2") (pinfunction "2_2") (pintype "passive"))
      (node (ref "U$69") (pin "6") (pinfunction "VBAT_6") (pintype "bidirectional"))
    )
    (net (code "86") (name "Net-(U$74-D)") (class "Default")
      (node (ref "U$2") (pin "P$2") (pinfunction "P$2_P$2") (pintype "bidirectional"))
      (node (ref "U$74") (pin "3") (pinfunction "D_3") (pintype "passive"))
    )
    (net (code "87") (name "Net-(U3-SDO)") (class "Default")
      (node (ref "SJ2") (pin "2") (pinfunction "2_2") (pintype "passive"))
      (node (ref "U3") (pin "5") (pinfunction "SDO_5") (pintype "output"))
    )
    (net (code "88") (name "Net-(U4-REGOUT)") (class "Default")
      (node (ref "C18") (pin "1") (pinfunction "1_1") (pintype "passive"))
      (node (ref "U4") (pin "10") (pinfunction "REGOUT_10") (pintype "bidirectional"))
    )
    (net (code "89") (name "SCL") (class "Default")
      (node (ref "R6") (pin "1") (pinfunction "1_1") (pintype "passive"))
      (node (ref "SCL") (pin "TP") (pinfunction "TP_TP") (pintype "input"))
      (node (ref "U$14") (pin "36") (pinfunction "P1.04_36") (pintype "bidirectional"))
      (node (ref "U$69") (pin "8") (pinfunction "SCL_8") (pintype "bidirectional"))
      (node (ref "U1") (pin "2") (pinfunction "SCL_2") (pintype "bidirectional"))
      (node (ref "U3") (pin "4") (pinfunction "SCK_4") (pintype "input"))
      (node (ref "U4") (pin "23") (pinfunction "SCL/SCLK_23") (pintype "bidirectional"))
    )
    (net (code "90") (name "SDA") (class "Default")
      (node (ref "R9") (pin "1") (pinfunction "1_1") (pintype "passive"))
      (node (ref "SDA") (pin "TP") (pinfunction "TP_TP") (pintype "input"))
      (node (ref "U$14") (pin "35") (pinfunction "P1.06_35") (pintype "bidirectional"))
      (node (ref "U$69") (pin "7") (pinfunction "SDA_7") (pintype "bidirectional"))
      (node (ref "U1") (pin "1") (pinfunction "SDA_1") (pintype "bidirectional"))
      (node (ref "U3") (pin "3") (pinfunction "SDI_3") (pintype "input"))
      (node (ref "U4") (pin "24") (pinfunction "SDA/SDI_24") (pintype "bidirectional"))
    )
    (net (code "91") (name "SHLD") (class "Default")
      (node (ref "J2") (pin "SHLD1") (pinfunction "SHLD_SHLD1") (pintype "bidirectional"))
      (node (ref "J2") (pin "SHLD2") (pinfunction "SHLD_SHLD2") (pintype "bidirectional"))
      (node (ref "J2") (pin "SHLD3") (pinfunction "SHLD_SHLD3") (pintype "bidirectional"))
      (node (ref "J2") (pin "SHLD4") (pinfunction "SHLD_SHLD4") (pintype "bidirectional"))
      (node (ref "J2") (pin "SHLD5") (pinfunction "SHLD_SHLD5") (pintype "bidirectional"))
      (node (ref "J2") (pin "SHLD6") (pinfunction "SHLD_SHLD6") (pintype "bidirectional"))
      (node (ref "J2") (pin "SHLD7") (pinfunction "SHLD_SHLD7") (pintype "bidirectional"))
      (node (ref "J2") (pin "SHLD8") (pinfunction "SHLD_SHLD8") (pintype "bidirectional"))
    )
    (net (code "92") (name "TS") (class "Default")
      (node (ref "R11") (pin "2") (pinfunction "2_2") (pintype "passive"))
      (node (ref "U1") (pin "10") (pinfunction "BIN_10") (pintype "bidirectional"))
    )
    (net (code "93") (name "USB_N") (class "Default")
      (node (ref "J2") (pin "A7") (pinfunction "D-_A7") (pintype "bidirectional"))
      (node (ref "J2") (pin "B7") (pinfunction "D-_B7") (pintype "bidirectional"))
      (node (ref "R15") (pin "1") (pinfunction "1_1") (pintype "passive"))
    )
    (net (code "94") (name "USB_P") (class "Default")
      (node (ref "J2") (pin "A6") (pinfunction "D+_A6") (pintype "bidirectional"))
      (node (ref "J2") (pin "B6") (pinfunction "D+_B6") (pintype "bidirectional"))
      (node (ref "R14") (pin "1") (pinfunction "1_1") (pintype "passive"))
    )
    (net (code "95") (name "VBAT") (class "Default")
      (node (ref "C1") (pin "1") (pinfunction "1_1") (pintype "passive"))
      (node (ref "Q3") (pin "3") (pinfunction "D_3") (pintype "passive"))
      (node (ref "R5") (pin "2") (pinfunction "2_2") (pintype "passive"))
      (node (ref "U$47") (pin "5") (pinfunction "BAT_5") (pintype "bidirectional"))
      (node (ref "U1") (pin "7") (pinfunction "SRN_7") (pintype "bidirectional"))
    )
    (net (code "96") (name "VBUS") (class "Default")
      (node (ref "C10") (pin "2") (pinfunction "2_2") (pintype "passive"))
      (node (ref "C9") (pin "1") (pinfunction "1_1") (pintype "passive"))
      (node (ref "D1") (pin "A") (pinfunction "A_A") (pintype "passive"))
      (node (ref "D3") (pin "A") (pinfunction "A_A") (pintype "passive"))
      (node (ref "D5") (pin "A") (pinfunction "A_A") (pintype "passive"))
      (node (ref "J2") (pin "VBUS1") (pinfunction "VBUS_VBUS1") (pintype "bidirectional"))
      (node (ref "J2") (pin "VBUS2") (pinfunction "VBUS_VBUS2") (pintype "bidirectional"))
      (node (ref "Q3") (pin "1") (pinfunction "G_1") (pintype "passive"))
      (node (ref "R2") (pin "2") (pinfunction "2_2") (pintype "passive"))
      (node (ref "U$14") (pin "47") (pinfunction "VBUS_47") (pintype "bidirectional"))
      (node (ref "U$47") (pin "4") (pinfunction "VCC_4") (pintype "bidirectional"))
      (node (ref "U$47") (pin "8") (pinfunction "CE_8") (pintype "bidirectional"))
    )
    (net (code "97") (name "unconnected-(DWN2-FRM-PadFRAME)") (class "Default")
      (node (ref "DWN2") (pin "FRAME") (pinfunction "FRM_FRAME") (pintype "bidirectional"))
    )
    (net (code "98") (name "unconnected-(J3-SWO-Pad6)") (class "Default")
      (node (ref "J3") (pin "6") (pinfunction "SWO_6") (pintype "bidirectional"))
    )
    (net (code "99") (name "unconnected-(LED1-RED_A-Pad2)") (class "Default")
      (node (ref "LED1") (pin "2") (pinfunction "RED_A_2") (pintype "bidirectional"))
    )
    (net (code "100") (name "unconnected-(U$7-MIC-PadP2)") (class "Default")
      (node (ref "U$7") (pin "P2") (pinfunction "MIC_P2") (pintype "bidirectional"))
    )
    (net (code "101") (name "unconnected-(U$7-MIC_VDD-PadP1)") (class "Default")
      (node (ref "U$7") (pin "P1") (pinfunction "MIC_VDD_P1") (pintype "bidirectional"))
    )
    (net (code "102") (name "unconnected-(U$17-PadHL)") (class "Default")
      (node (ref "U$17") (pin "HL") (pinfunction "HL_HL") (pintype "bidirectional"))
    )
    (net (code "103") (name "unconnected-(U$17-PadHR)") (class "Default")
      (node (ref "U$17") (pin "HR") (pinfunction "HR_HR") (pintype "bidirectional"))
    )
    (net (code "104") (name "unconnected-(U$45-PadO)") (class "Default")
      (node (ref "U$45") (pin "O") (pinfunction "O_O") (pintype "passive"))
    )
    (net (code "105") (name "unconnected-(U$46-PadPLANE)") (class "Default")
      (node (ref "U$46") (pin "PLANE") (pinfunction "PLANE_PLANE") (pintype "bidirectional"))
    )
    (net (code "106") (name "unconnected-(U$69-32KHZ-Pad1)") (class "Default")
      (node (ref "U$69") (pin "1") (pinfunction "32KHZ_1") (pintype "bidirectional"))
    )
    (net (code "107") (name "unconnected-(U$69-~{RST}-Pad4)") (class "Default")
      (node (ref "U$69") (pin "4") (pinfunction "~{RST}_4") (pintype "bidirectional"))
    )
    (net (code "108") (name "unconnected-(U4-NC-Pad2)") (class "Default")
      (node (ref "U4") (pin "2") (pinfunction "NC_2") (pintype "bidirectional"))
    )
    (net (code "109") (name "unconnected-(U4-NC-Pad3)") (class "Default")
      (node (ref "U4") (pin "3") (pinfunction "NC_3") (pintype "bidirectional"))
    )
    (net (code "110") (name "unconnected-(U4-NC-Pad4)") (class "Default")
      (node (ref "U4") (pin "4") (pinfunction "NC_4") (pintype "bidirectional"))
    )
    (net (code "111") (name "unconnected-(U4-NC-Pad5)") (class "Default")
      (node (ref "U4") (pin "5") (pinfunction "NC_5") (pintype "bidirectional"))
    )
    (net (code "112") (name "unconnected-(U4-NC-Pad6)") (class "Default")
      (node (ref "U4") (pin "6") (pinfunction "NC_6") (pintype "bidirectional"))
    )
    (net (code "113") (name "unconnected-(U4-NC-Pad14)") (class "Default")
      (node (ref "U4") (pin "14") (pinfunction "NC_14") (pintype "bidirectional"))
    )
    (net (code "114") (name "unconnected-(U4-NC-Pad15)") (class "Default")
      (node (ref "U4") (pin "15") (pinfunction "NC_15") (pintype "bidirectional"))
    )
    (net (code "115") (name "unconnected-(U4-NC-Pad16)") (class "Default")
      (node (ref "U4") (pin "16") (pinfunction "NC_16") (pintype "bidirectional"))
    )
    (net (code "116") (name "unconnected-(U4-NC-Pad17)") (class "Default")
      (node (ref "U4") (pin "17") (pinfunction "NC_17") (pintype "bidirectional"))
    )
    (net (code "117") (name "unconnected-(U4-RESV-Pad19)") (class "Default")
      (node (ref "U4") (pin "19") (pinfunction "RESV_19") (pintype "bidirectional"))
    )
    (net (code "118") (name "unconnected-(X4-CARD_DETECT1-PadCD2)") (class "Default")
      (node (ref "X4") (pin "CD2") (pinfunction "CARD_DETECT1_CD2") (pintype "passive"))
    )
    (net (code "119") (name "unconnected-(X4-DAT1-Pad8)") (class "Default")
      (node (ref "X4") (pin "8") (pinfunction "DAT1_8") (pintype "bidirectional"))
    )
    (net (code "120") (name "unconnected-(X4-DAT2-Pad1)") (class "Default")
      (node (ref "X4") (pin "1") (pinfunction "DAT2_1") (pintype "bidirectional"))
    )
  )
)
